# Schematic.net
KiCad netlist of a schematic drawn in EAGLE
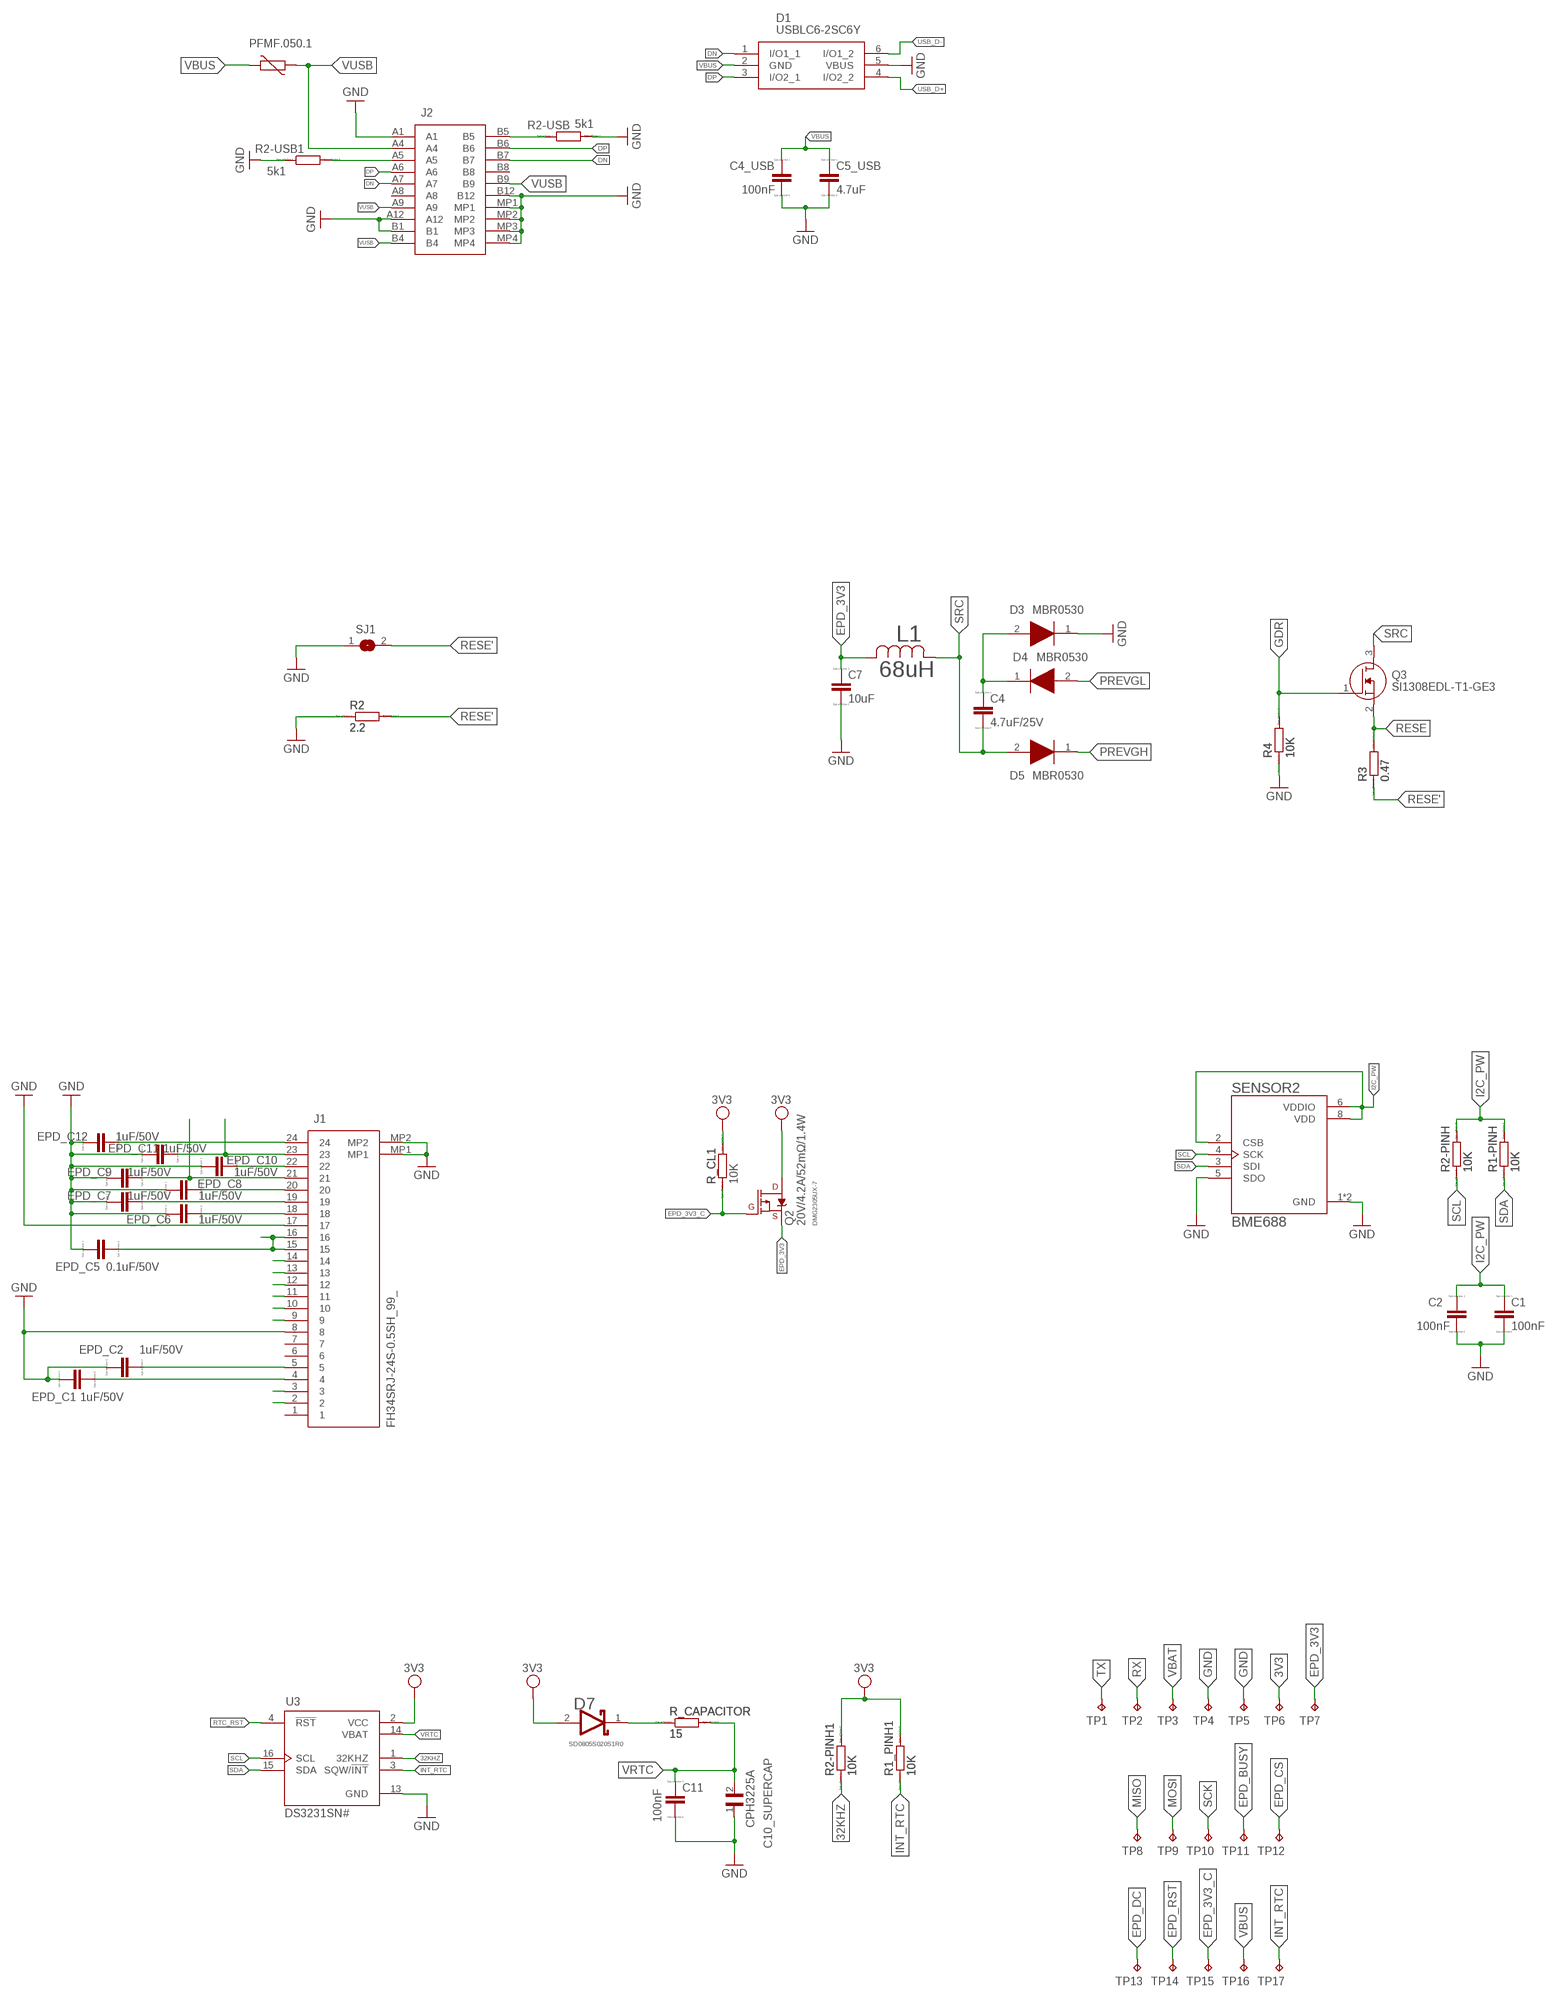
[diagram p0: schematic, sheet 1, part 1 of 2]
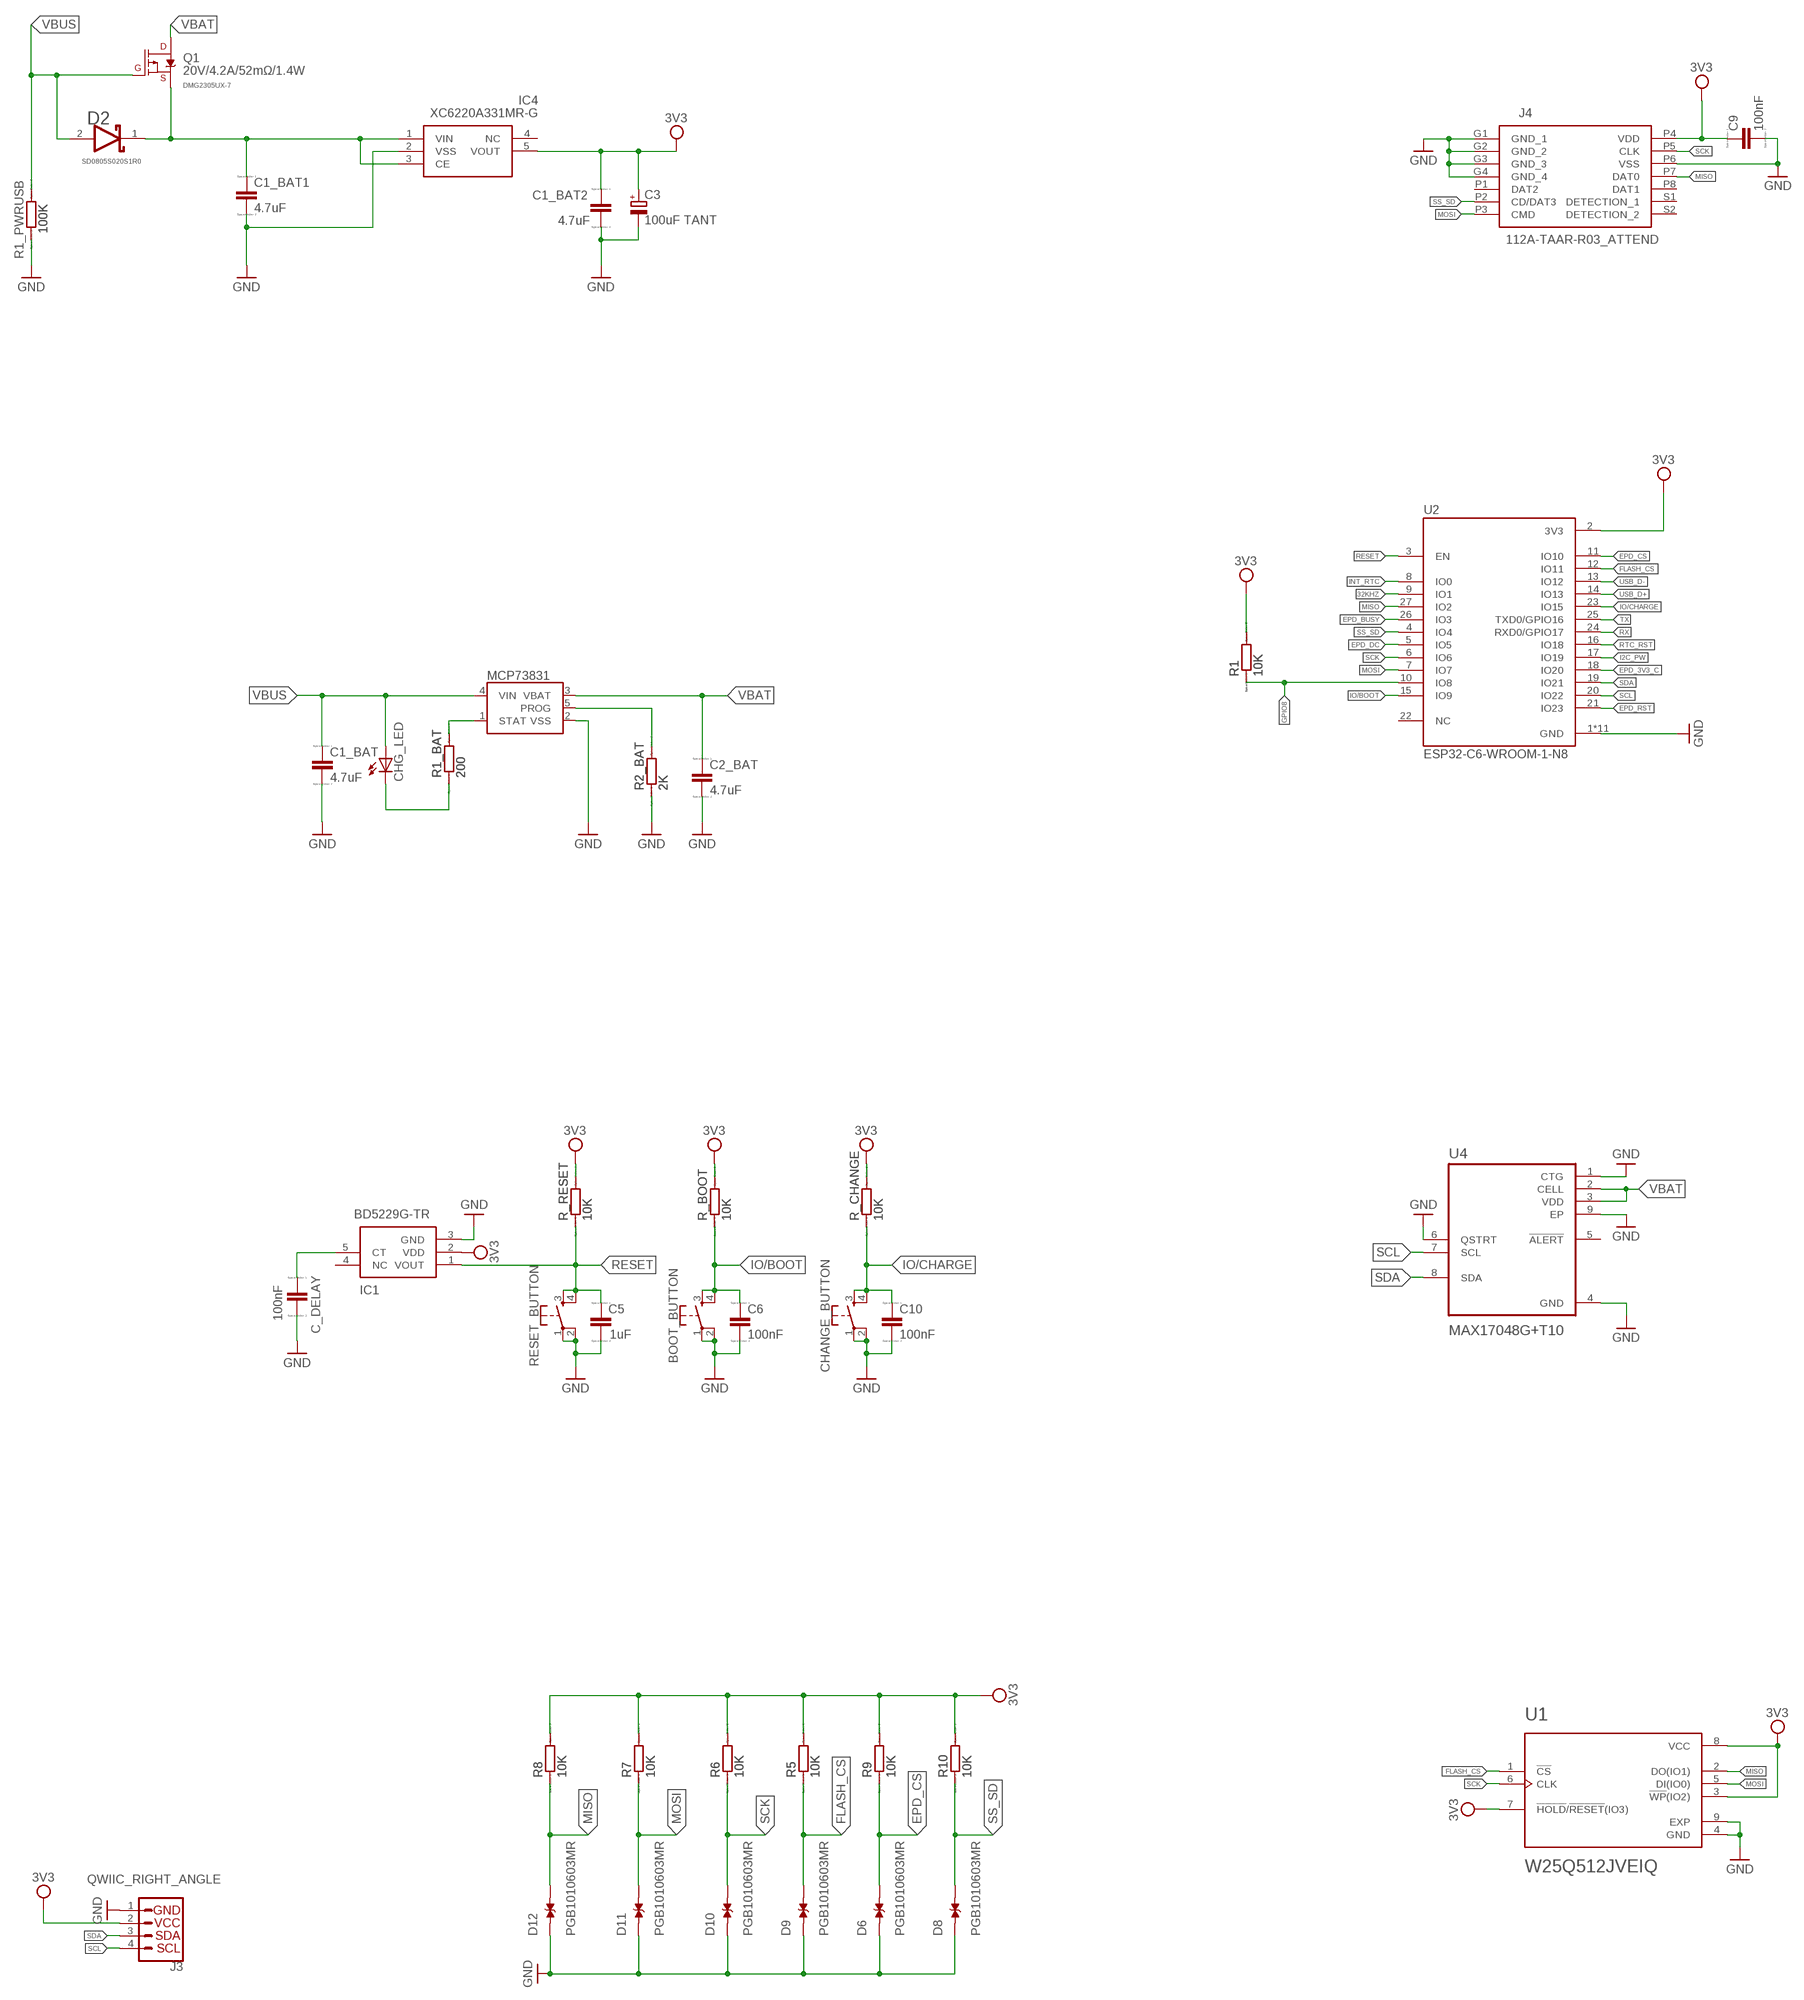
[diagram p1: schematic, sheet 1, part 2 of 2]

(export (version "E")
  (design (tool "Eeschema 10.0.6"))
  (components
    (comp (ref "BOOT_BUTTON")
      (value "BUTTON_CUSYOMV1")
      (footprint "eagle-import:MYBUTTON")
      (libsource (lib "eagle-import") (part "BUTTON_CUSYOMV1"))
    )
    (comp (ref "C1")
      (value "100nF")
      (footprint "eagle-import:EAGLE-LTSPICE_C0402")
      (libsource (lib "eagle-import") (part "EAGLE-LTSPICE_CC0402"))
    )
    (comp (ref "C1_BAT")
      (value "4.7uF")
      (footprint "eagle-import:EAGLE-LTSPICE_C0402")
      (libsource (lib "eagle-import") (part "EAGLE-LTSPICE_CC0402"))
    )
    (comp (ref "C1_BAT1")
      (value "4.7uF")
      (footprint "eagle-import:EAGLE-LTSPICE_C0402")
      (libsource (lib "eagle-import") (part "EAGLE-LTSPICE_CC0402"))
    )
    (comp (ref "C1_BAT2")
      (value "4.7uF")
      (footprint "eagle-import:EAGLE-LTSPICE_C0402")
      (libsource (lib "eagle-import") (part "EAGLE-LTSPICE_CC0402"))
    )
    (comp (ref "C2")
      (value "100nF")
      (footprint "eagle-import:EAGLE-LTSPICE_C0402")
      (libsource (lib "eagle-import") (part "EAGLE-LTSPICE_CC0402"))
    )
    (comp (ref "C2_BAT")
      (value "4.7uF")
      (footprint "eagle-import:EAGLE-LTSPICE_C0402")
      (libsource (lib "eagle-import") (part "EAGLE-LTSPICE_CC0402"))
    )
    (comp (ref "C3")
      (value "100uF TANT")
      (footprint "eagle-import:RCL_CT3528")
      (libsource (lib "eagle-import") (part "RCL_CPOL-EUCT3528"))
    )
    (comp (ref "C4")
      (value "4.7uF/25V")
      (footprint "eagle-import:ESP32_WROVER_EAGLE-LTSPICE_C0402")
      (libsource (lib "eagle-import") (part "ESP32_WROVER_EAGLE-LTSPICE_CC0402"))
    )
    (comp (ref "C4_USB")
      (value "100nF")
      (footprint "eagle-import:EAGLE-LTSPICE_C0402")
      (libsource (lib "eagle-import") (part "EAGLE-LTSPICE_CC0402"))
    )
    (comp (ref "C5")
      (value "1uF")
      (footprint "eagle-import:EAGLE-LTSPICE_C0402")
      (libsource (lib "eagle-import") (part "EAGLE-LTSPICE_CC0402"))
    )
    (comp (ref "C5_USB")
      (value "4.7uF")
      (footprint "eagle-import:EAGLE-LTSPICE_C0402")
      (libsource (lib "eagle-import") (part "EAGLE-LTSPICE_CC0402"))
    )
    (comp (ref "C6")
      (value "100nF")
      (footprint "eagle-import:EAGLE-LTSPICE_C0402")
      (libsource (lib "eagle-import") (part "EAGLE-LTSPICE_CC0402"))
    )
    (comp (ref "C7")
      (value "10uF")
      (footprint "eagle-import:ESP32_WROVER_EAGLE-LTSPICE_C0402")
      (libsource (lib "eagle-import") (part "ESP32_WROVER_EAGLE-LTSPICE_CC0402"))
    )
    (comp (ref "C9")
      (value "100nF")
      (footprint "eagle-import:ESP32_WROVER_EAGLE-LTSPICE_C0402")
      (libsource (lib "eagle-import") (part "ESP32_WROVER_EAGLE-LTSPICE_CC0402"))
    )
    (comp (ref "C10")
      (value "100nF")
      (footprint "eagle-import:EAGLE-LTSPICE_C0402")
      (libsource (lib "eagle-import") (part "EAGLE-LTSPICE_CC0402"))
    )
    (comp (ref "C10_SUPERCAP")
      (value "CPH3225A")
      (footprint "eagle-import:CAPCP3225X100N")
      (fields (field (name "MF") "Seiko Instruments"))
      (libsource (lib "eagle-import") (part "CPH3225A"))
    )
    (comp (ref "C11")
      (value "100nF")
      (footprint "eagle-import:EAGLE-LTSPICE_C0402")
      (libsource (lib "eagle-import") (part "EAGLE-LTSPICE_CC0402"))
    )
    (comp (ref "CHANGE_BUTTON")
      (value "BUTTON_CUSYOMV1")
      (footprint "eagle-import:MYBUTTON")
      (libsource (lib "eagle-import") (part "BUTTON_CUSYOMV1"))
    )
    (comp (ref "CHG_LED")
      (value "ADAFRUIT_LEDCHIP-LED0603")
      (footprint "eagle-import:ADAFRUIT_CHIP-LED0603")
      (libsource (lib "eagle-import") (part "ADAFRUIT_LEDCHIP-LED0603"))
    )
    (comp (ref "C_DELAY")
      (value "100nF")
      (footprint "eagle-import:EAGLE-LTSPICE_C0402")
      (libsource (lib "eagle-import") (part "EAGLE-LTSPICE_CC0402"))
    )
    (comp (ref "D1")
      (value "USBLC6-2SC6Y")
      (footprint "eagle-import:SOT95P280X145-6N")
      (fields (field (name "MF") "STMicroelectronics"))
      (libsource (lib "eagle-import") (part "USBLC6-2SC6Y"))
    )
    (comp (ref "D2")
      (value "SD0805S020S1R0")
      (footprint "eagle-import:ESP32_WROVER_AVX---SD0805S020S1R0_AVX_SD0805S020S1R0_0")
      (fields
        (field (name "DIGIKEY_PART_NUMBER") "478-7800-1-ND")
        (field (name "MF") "AVX")
        (field (name "MOUSER_PART_NUMBER") "581-SD0805S020S1R0")
      )
      (libsource (lib "eagle-import") (part "ESP32_WROVER_AVX---SD0805S020S1R0_AVX_SD0805S020S1R0_0_0AVX_SD0805S020S1R0_0_0"))
    )
    (comp (ref "D3")
      (value "MBR0530")
      (footprint "eagle-import:SOD3716X135N")
      (fields (field (name "MF") "ON Semiconductor"))
      (libsource (lib "eagle-import") (part "MBR0530"))
    )
    (comp (ref "D4")
      (value "MBR0530")
      (footprint "eagle-import:SOD3716X135N")
      (fields (field (name "MF") "ON Semiconductor"))
      (libsource (lib "eagle-import") (part "MBR0530"))
    )
    (comp (ref "D5")
      (value "MBR0530")
      (footprint "eagle-import:SOD3716X135N")
      (fields (field (name "MF") "ON Semiconductor"))
      (libsource (lib "eagle-import") (part "MBR0530"))
    )
    (comp (ref "D6")
      (value "PGB1010603MR")
      (footprint "eagle-import:DIOC1608X36N")
      (fields (field (name "MF") "Littelfuse Inc."))
      (libsource (lib "eagle-import") (part "PGB1010603MR"))
    )
    (comp (ref "D7")
      (value "SD0805S020S1R0")
      (footprint "eagle-import:ESP32_WROVER_AVX---SD0805S020S1R0_AVX_SD0805S020S1R0_0")
      (fields
        (field (name "DIGIKEY_PART_NUMBER") "478-7800-1-ND")
        (field (name "MF") "AVX")
        (field (name "MOUSER_PART_NUMBER") "581-SD0805S020S1R0")
      )
      (libsource (lib "eagle-import") (part "ESP32_WROVER_AVX---SD0805S020S1R0_AVX_SD0805S020S1R0_0_0AVX_SD0805S020S1R0_0_0"))
    )
    (comp (ref "D8")
      (value "PGB1010603MR")
      (footprint "eagle-import:DIOC1608X36N")
      (fields (field (name "MF") "Littelfuse Inc."))
      (libsource (lib "eagle-import") (part "PGB1010603MR"))
    )
    (comp (ref "D9")
      (value "PGB1010603MR")
      (footprint "eagle-import:DIOC1608X36N")
      (fields (field (name "MF") "Littelfuse Inc."))
      (libsource (lib "eagle-import") (part "PGB1010603MR"))
    )
    (comp (ref "D10")
      (value "PGB1010603MR")
      (footprint "eagle-import:DIOC1608X36N")
      (fields (field (name "MF") "Littelfuse Inc."))
      (libsource (lib "eagle-import") (part "PGB1010603MR"))
    )
    (comp (ref "D11")
      (value "PGB1010603MR")
      (footprint "eagle-import:DIOC1608X36N")
      (fields (field (name "MF") "Littelfuse Inc."))
      (libsource (lib "eagle-import") (part "PGB1010603MR"))
    )
    (comp (ref "D12")
      (value "PGB1010603MR")
      (footprint "eagle-import:DIOC1608X36N")
      (fields (field (name "MF") "Littelfuse Inc."))
      (libsource (lib "eagle-import") (part "PGB1010603MR"))
    )
    (comp (ref "EPD_C1")
      (value "1uF/50V")
      (footprint "eagle-import:EAGLE-LTSPICE_C0402")
      (libsource (lib "eagle-import") (part "EAGLE-LTSPICE_CC0402"))
    )
    (comp (ref "EPD_C2")
      (value "1uF/50V")
      (footprint "eagle-import:EAGLE-LTSPICE_C0402")
      (libsource (lib "eagle-import") (part "EAGLE-LTSPICE_CC0402"))
    )
    (comp (ref "EPD_C5")
      (value "0.1uF/50V")
      (footprint "eagle-import:EAGLE-LTSPICE_C0402")
      (libsource (lib "eagle-import") (part "EAGLE-LTSPICE_CC0402"))
    )
    (comp (ref "EPD_C6")
      (value "1uF/50V")
      (footprint "eagle-import:EAGLE-LTSPICE_C0402")
      (libsource (lib "eagle-import") (part "EAGLE-LTSPICE_CC0402"))
    )
    (comp (ref "EPD_C7")
      (value "1uF/50V")
      (footprint "eagle-import:EAGLE-LTSPICE_C0402")
      (libsource (lib "eagle-import") (part "EAGLE-LTSPICE_CC0402"))
    )
    (comp (ref "EPD_C8")
      (value "1uF/50V")
      (footprint "eagle-import:EAGLE-LTSPICE_C0402")
      (libsource (lib "eagle-import") (part "EAGLE-LTSPICE_CC0402"))
    )
    (comp (ref "EPD_C9")
      (value "1uF/50V")
      (footprint "eagle-import:EAGLE-LTSPICE_C0402")
      (libsource (lib "eagle-import") (part "EAGLE-LTSPICE_CC0402"))
    )
    (comp (ref "EPD_C10")
      (value "1uF/50V")
      (footprint "eagle-import:EAGLE-LTSPICE_C0402")
      (libsource (lib "eagle-import") (part "EAGLE-LTSPICE_CC0402"))
    )
    (comp (ref "EPD_C11")
      (value "1uF/50V")
      (footprint "eagle-import:EAGLE-LTSPICE_C0402")
      (libsource (lib "eagle-import") (part "EAGLE-LTSPICE_CC0402"))
    )
    (comp (ref "EPD_C12")
      (value "1uF/50V")
      (footprint "eagle-import:EAGLE-LTSPICE_C0402")
      (libsource (lib "eagle-import") (part "EAGLE-LTSPICE_CC0402"))
    )
    (comp (ref "IC1")
      (value "BD5229G-TR")
      (footprint "eagle-import:SOT95P280X125-5N")
      (fields (field (name "MOUSER_PART_NUMBER") "755-BD5229G-TR"))
      (libsource (lib "eagle-import") (part "BD5229G-TR"))
    )
    (comp (ref "IC4")
      (value "XC6220A331MR-G")
      (footprint "eagle-import:SOT95P280X120-5N")
      (fields (field (name "MOUSER_PART_NUMBER") "865-XC6220A331MR-G"))
      (libsource (lib "eagle-import") (part "XC6220A331MR-G"))
    )
    (comp (ref "J1")
      (value "FH34SRJ-24S-0.5SH_99_")
      (footprint "eagle-import:FH34SRJ24S05SH99")
      (fields
        (field (name "MANUFACTURER_PART_NUMBER") "FH34SRJ-24S-0.5SH(99)")
        (field (name "MOUSER_PART_NUMBER") "798-FH34SRJ24S05SH99")
      )
      (libsource (lib "eagle-import") (part "FH34SRJ-24S-0.5SH_99_"))
    )
    (comp (ref "J2")
      (value "SAMACSYS_PARTS_USB4110-GF-A")
      (footprint "eagle-import:SAMACSYS_PARTS_USB4110GFA")
      (fields
        (field (name "MANUFACTURER_PART_NUMBER") "USB4110-GF-A")
        (field (name "MOUSER_PART_NUMBER") "640-USB4110-GF-A")
      )
      (libsource (lib "eagle-import") (part "SAMACSYS_PARTS_USB4110-GF-A"))
    )
    (comp (ref "J3")
      (value "QWIIC_RIGHT_ANGLE")
      (footprint "eagle-import:JST04_1MM_RA")
      (libsource (lib "eagle-import") (part "QWIIC_CONNECTORJS-1MM"))
    )
    (comp (ref "J4")
      (value "112A-TAAR-R03_ATTEND")
      (footprint "eagle-import:112ATAARR03ATTEND")
      (fields (field (name "MANUFACTURER_PART_NUMBER") "112A-TAAR-R03 ATTEND"))
      (libsource (lib "eagle-import") (part "112A-TAAR-R03_ATTEND"))
    )
    (comp (ref "L1")
      (value "68uH")
      (footprint "eagle-import:IND_4828-WE-TPC_WRE")
      (fields
        (field (name "MANUFACTURER_PART_NUMBER") "744043680")
        (field (name "COPYRIGHT") "Copyright (C) 2024 Ultra Librarian. All rights reserved.")
      )
      (libsource (lib "eagle-import") (part "744043680IND_4828-WE-TPC_WRE"))
    )
    (comp (ref "MCP73831")
      (value "ESP32_WROVER_SPARKFUN-IC-POWER_MCP73831")
      (footprint "eagle-import:ESP32_WROVER_SPARKFUN-IC-POWER_SOT23-5")
      (libsource (lib "eagle-import") (part "ESP32_WROVER_SPARKFUN-IC-POWER_MCP73831"))
    )
    (comp (ref "PFMF.050.1")
      (value "ESP32C6_VARISTORCN1812")
      (footprint "eagle-import:ESP32C6_VARISTOR_CT_CN1812")
      (libsource (lib "eagle-import") (part "ESP32C6_VARISTORCN1812"))
    )
    (comp (ref "Q1")
      (value "20V/4.2A/52mΩ/1.4W")
      (footprint "eagle-import:ESP32_WROVER_SPARKFUN-DISCRETESEMI_SOT23-3")
      (libsource (lib "eagle-import") (part "ESP32_WROVER_SPARKFUN-DISCRETESEMI_MOSFET_PCH-DMG2305UX-7"))
    )
    (comp (ref "Q2")
      (value "20V/4.2A/52mΩ/1.4W")
      (footprint "eagle-import:ESP32_WROVER_SPARKFUN-DISCRETESEMI_SOT23-3")
      (libsource (lib "eagle-import") (part "ESP32_WROVER_SPARKFUN-DISCRETESEMI_MOSFET_PCH-DMG2305UX-7"))
    )
    (comp (ref "Q3")
      (value "SI1308EDL-T1-GE3")
      (footprint "eagle-import:SOT65P210X110-3N")
      (fields (field (name "MF") "Vishay Siliconix"))
      (libsource (lib "eagle-import") (part "SI1308EDL-T1-GE3"))
    )
    (comp (ref "R1")
      (value "10K")
      (footprint "eagle-import:ESP32_WROVER_EAGLE-LTSPICE_R0402")
      (libsource (lib "eagle-import") (part "ESP32_WROVER_EAGLE-LTSPICE_RR0402"))
    )
    (comp (ref "R1-PINH")
      (value "10K")
      (footprint "eagle-import:ESP32_WROVER_EAGLE-LTSPICE_R0402")
      (libsource (lib "eagle-import") (part "ESP32_WROVER_EAGLE-LTSPICE_RR0402"))
    )
    (comp (ref "R1_BAT")
      (value "200")
      (footprint "eagle-import:ESP32_WROVER_EAGLE-LTSPICE_R0402")
      (libsource (lib "eagle-import") (part "ESP32_WROVER_EAGLE-LTSPICE_RR0402"))
    )
    (comp (ref "R1_PINH1")
      (value "10K")
      (footprint "eagle-import:ESP32_WROVER_EAGLE-LTSPICE_R0402")
      (libsource (lib "eagle-import") (part "ESP32_WROVER_EAGLE-LTSPICE_RR0402"))
    )
    (comp (ref "R1_PWRUSB")
      (value "100K")
      (footprint "eagle-import:ESP32_WROVER_EAGLE-LTSPICE_R0402")
      (libsource (lib "eagle-import") (part "ESP32_WROVER_EAGLE-LTSPICE_RR0402"))
    )
    (comp (ref "R2")
      (value "2.2")
      (footprint "eagle-import:ESP32_WROVER_EAGLE-LTSPICE_R0402")
      (libsource (lib "eagle-import") (part "ESP32_WROVER_EAGLE-LTSPICE_RR0402"))
    )
    (comp (ref "R2-PINH")
      (value "10K")
      (footprint "eagle-import:ESP32_WROVER_EAGLE-LTSPICE_R0402")
      (libsource (lib "eagle-import") (part "ESP32_WROVER_EAGLE-LTSPICE_RR0402"))
    )
    (comp (ref "R2-PINH1")
      (value "10K")
      (footprint "eagle-import:ESP32_WROVER_EAGLE-LTSPICE_R0402")
      (libsource (lib "eagle-import") (part "ESP32_WROVER_EAGLE-LTSPICE_RR0402"))
    )
    (comp (ref "R2-USB")
      (value "5k1")
      (footprint "eagle-import:ESP32_WROVER_EAGLE-LTSPICE_R0402")
      (libsource (lib "eagle-import") (part "ESP32_WROVER_EAGLE-LTSPICE_RR0402"))
    )
    (comp (ref "R2-USB1")
      (value "5k1")
      (footprint "eagle-import:ESP32_WROVER_EAGLE-LTSPICE_R0402")
      (libsource (lib "eagle-import") (part "ESP32_WROVER_EAGLE-LTSPICE_RR0402"))
    )
    (comp (ref "R2_BAT")
      (value "2K")
      (footprint "eagle-import:ESP32_WROVER_EAGLE-LTSPICE_R0402")
      (libsource (lib "eagle-import") (part "ESP32_WROVER_EAGLE-LTSPICE_RR0402"))
    )
    (comp (ref "R3")
      (value "0.47")
      (footprint "eagle-import:ESP32_WROVER_EAGLE-LTSPICE_R0402")
      (libsource (lib "eagle-import") (part "ESP32_WROVER_EAGLE-LTSPICE_RR0402"))
    )
    (comp (ref "R4")
      (value "10K")
      (footprint "eagle-import:ESP32_WROVER_EAGLE-LTSPICE_R0402")
      (libsource (lib "eagle-import") (part "ESP32_WROVER_EAGLE-LTSPICE_RR0402"))
    )
    (comp (ref "R5")
      (value "10K")
      (footprint "eagle-import:ESP32_WROVER_EAGLE-LTSPICE_R0402")
      (libsource (lib "eagle-import") (part "ESP32_WROVER_EAGLE-LTSPICE_RR0402"))
    )
    (comp (ref "R6")
      (value "10K")
      (footprint "eagle-import:ESP32_WROVER_EAGLE-LTSPICE_R0402")
      (libsource (lib "eagle-import") (part "ESP32_WROVER_EAGLE-LTSPICE_RR0402"))
    )
    (comp (ref "R7")
      (value "10K")
      (footprint "eagle-import:ESP32_WROVER_EAGLE-LTSPICE_R0402")
      (libsource (lib "eagle-import") (part "ESP32_WROVER_EAGLE-LTSPICE_RR0402"))
    )
    (comp (ref "R8")
      (value "10K")
      (footprint "eagle-import:ESP32_WROVER_EAGLE-LTSPICE_R0402")
      (libsource (lib "eagle-import") (part "ESP32_WROVER_EAGLE-LTSPICE_RR0402"))
    )
    (comp (ref "R9")
      (value "10K")
      (footprint "eagle-import:ESP32_WROVER_EAGLE-LTSPICE_R0402")
      (libsource (lib "eagle-import") (part "ESP32_WROVER_EAGLE-LTSPICE_RR0402"))
    )
    (comp (ref "R10")
      (value "10K")
      (footprint "eagle-import:ESP32_WROVER_EAGLE-LTSPICE_R0402")
      (libsource (lib "eagle-import") (part "ESP32_WROVER_EAGLE-LTSPICE_RR0402"))
    )
    (comp (ref "RESET_BUTTON")
      (value "BUTTON_CUSYOMV1")
      (footprint "eagle-import:MYBUTTON")
      (libsource (lib "eagle-import") (part "BUTTON_CUSYOMV1"))
    )
    (comp (ref "R_BOOT")
      (value "10K")
      (footprint "eagle-import:ESP32_WROVER_EAGLE-LTSPICE_R0402")
      (libsource (lib "eagle-import") (part "ESP32_WROVER_EAGLE-LTSPICE_RR0402"))
    )
    (comp (ref "R_CAPACITOR")
      (value "15")
      (footprint "eagle-import:ESP32_WROVER_EAGLE-LTSPICE_R0402")
      (libsource (lib "eagle-import") (part "ESP32_WROVER_EAGLE-LTSPICE_RR0402"))
    )
    (comp (ref "R_CHANGE")
      (value "10K")
      (footprint "eagle-import:ESP32_WROVER_EAGLE-LTSPICE_R0402")
      (libsource (lib "eagle-import") (part "ESP32_WROVER_EAGLE-LTSPICE_RR0402"))
    )
    (comp (ref "R_CL1")
      (value "10K")
      (footprint "eagle-import:ESP32_WROVER_EAGLE-LTSPICE_R0402")
      (libsource (lib "eagle-import") (part "ESP32_WROVER_EAGLE-LTSPICE_RR0402"))
    )
    (comp (ref "R_RESET")
      (value "10K")
      (footprint "eagle-import:ESP32_WROVER_EAGLE-LTSPICE_R0402")
      (libsource (lib "eagle-import") (part "ESP32_WROVER_EAGLE-LTSPICE_RR0402"))
    )
    (comp (ref "SENSOR2")
      (value "BME688")
      (footprint "eagle-import:ESP32_WROVER_BME680_PSON80P300X300X100-8N")
      (fields (field (name "MF") "Bosch Sensortec") (field (name "MP") "BME680"))
      (libsource (lib "eagle-import") (part "ESP32_WROVER_BME680_BME680"))
    )
    (comp (ref "SJ1") (value "SJ") (footprint "eagle-import:SJ") (libsource (lib "eagle-import") (part "SJ")))
    (comp (ref "TP1")
      (value "TPTP20R")
      (footprint "eagle-import:TP20R")
      (libsource (lib "eagle-import") (part "TPTP20R"))
    )
    (comp (ref "TP2")
      (value "TPTP20R")
      (footprint "eagle-import:TP20R")
      (libsource (lib "eagle-import") (part "TPTP20R"))
    )
    (comp (ref "TP3")
      (value "TPTP20R")
      (footprint "eagle-import:TP20R")
      (libsource (lib "eagle-import") (part "TPTP20R"))
    )
    (comp (ref "TP4")
      (value "TPTP20R")
      (footprint "eagle-import:TP20R")
      (libsource (lib "eagle-import") (part "TPTP20R"))
    )
    (comp (ref "TP5")
      (value "TPTP20R")
      (footprint "eagle-import:TP20R")
      (libsource (lib "eagle-import") (part "TPTP20R"))
    )
    (comp (ref "TP6")
      (value "TPTP20R")
      (footprint "eagle-import:TP20R")
      (libsource (lib "eagle-import") (part "TPTP20R"))
    )
    (comp (ref "TP7")
      (value "TPTP20R")
      (footprint "eagle-import:TP20R")
      (libsource (lib "eagle-import") (part "TPTP20R"))
    )
    (comp (ref "TP8")
      (value "TPTP20R")
      (footprint "eagle-import:TP20R")
      (libsource (lib "eagle-import") (part "TPTP20R"))
    )
    (comp (ref "TP9")
      (value "TPTP20R")
      (footprint "eagle-import:TP20R")
      (libsource (lib "eagle-import") (part "TPTP20R"))
    )
    (comp (ref "TP10")
      (value "TPTP20R")
      (footprint "eagle-import:TP20R")
      (libsource (lib "eagle-import") (part "TPTP20R"))
    )
    (comp (ref "TP11")
      (value "TPTP20R")
      (footprint "eagle-import:TP20R")
      (libsource (lib "eagle-import") (part "TPTP20R"))
    )
    (comp (ref "TP12")
      (value "TPTP20R")
      (footprint "eagle-import:TP20R")
      (libsource (lib "eagle-import") (part "TPTP20R"))
    )
    (comp (ref "TP13")
      (value "TPTP20R")
      (footprint "eagle-import:TP20R")
      (libsource (lib "eagle-import") (part "TPTP20R"))
    )
    (comp (ref "TP14")
      (value "TPTP20R")
      (footprint "eagle-import:TP20R")
      (libsource (lib "eagle-import") (part "TPTP20R"))
    )
    (comp (ref "TP15")
      (value "TPTP20R")
      (footprint "eagle-import:TP20R")
      (libsource (lib "eagle-import") (part "TPTP20R"))
    )
    (comp (ref "TP16")
      (value "TPTP20R")
      (footprint "eagle-import:TP20R")
      (libsource (lib "eagle-import") (part "TPTP20R"))
    )
    (comp (ref "TP17")
      (value "TPTP20R")
      (footprint "eagle-import:TP20R")
      (libsource (lib "eagle-import") (part "TPTP20R"))
    )
    (comp (ref "U1")
      (value "W25Q512JVEIQ")
      (footprint "eagle-import:SON127P600X800X80-9N")
      (fields (field (name "MF") "Winbond Electronics"))
      (libsource (lib "eagle-import") (part "W25Q512JVEIQ"))
    )
    (comp (ref "U2")
      (value "ESP32-C6-WROOM-1-N8")
      (footprint "eagle-import:XCVR_ESP32-C6-WROOM-1-N8")
      (fields (field (name "MF") "Espressif Systems"))
      (libsource (lib "eagle-import") (part "ESP32-C6-WROOM-1-N8"))
    )
    (comp (ref "U3")
      (value "DS3231SN#")
      (footprint "eagle-import:SOIC127P1032X265-16N")
      (fields (field (name "MF") "Analog Devices"))
      (libsource (lib "eagle-import") (part "DS3231SN#"))
    )
    (comp (ref "U4")
      (value "MAX17048G+T10")
      (footprint "eagle-import:SON50P200X200X80-9N")
      (fields (field (name "MF") "Analog Devices"))
      (libsource (lib "eagle-import") (part "MAX17048G+T10"))
    )
  )
  (nets
    (net (code "1") (name "3V3") (class "Default")
      (node (ref "C1_BAT2") (pin "1") (pinfunction "1_1") (pintype "passive"))
      (node (ref "C3") (pin "+") (pinfunction "+_+") (pintype "passive"))
      (node (ref "C9") (pin "1") (pinfunction "1_1") (pintype "passive"))
      (node (ref "D7") (pin "2") (pinfunction "ANODE_2") (pintype "bidirectional"))
      (node (ref "IC1") (pin "2") (pinfunction "VDD_2") (pintype "bidirectional"))
      (node (ref "IC4") (pin "5") (pinfunction "VOUT_5") (pintype "bidirectional"))
      (node (ref "J3") (pin "2") (pinfunction "2_2") (pintype "power_in"))
      (node (ref "J4") (pin "P4") (pinfunction "VDD_P4") (pintype "bidirectional"))
      (node (ref "Q2") (pin "3") (pinfunction "D_3") (pintype "bidirectional"))
      (node (ref "R1") (pin "2") (pinfunction "2_2") (pintype "passive"))
      (node (ref "R10") (pin "2") (pinfunction "2_2") (pintype "passive"))
      (node (ref "R1_PINH1") (pin "2") (pinfunction "2_2") (pintype "passive"))
      (node (ref "R2-PINH1") (pin "2") (pinfunction "2_2") (pintype "passive"))
      (node (ref "R5") (pin "2") (pinfunction "2_2") (pintype "passive"))
      (node (ref "R6") (pin "2") (pinfunction "2_2") (pintype "passive"))
      (node (ref "R7") (pin "2") (pinfunction "2_2") (pintype "passive"))
      (node (ref "R8") (pin "2") (pinfunction "2_2") (pintype "passive"))
      (node (ref "R9") (pin "2") (pinfunction "2_2") (pintype "passive"))
      (node (ref "R_BOOT") (pin "2") (pinfunction "2_2") (pintype "passive"))
      (node (ref "R_CHANGE") (pin "2") (pinfunction "2_2") (pintype "passive"))
      (node (ref "R_CL1") (pin "2") (pinfunction "2_2") (pintype "passive"))
      (node (ref "R_RESET") (pin "2") (pinfunction "2_2") (pintype "passive"))
      (node (ref "TP6") (pin "TP") (pinfunction "TP_TP") (pintype "input"))
      (node (ref "U1") (pin "3") (pinfunction "~{WP}(IO2)_3") (pintype "bidirectional"))
      (node (ref "U1") (pin "7") (pinfunction "~{HOLD}/~{RESET}(IO3)_7") (pintype "bidirectional"))
      (node (ref "U1") (pin "8") (pinfunction "VCC_8") (pintype "power_in"))
      (node (ref "U2") (pin "2") (pinfunction "3V3_2") (pintype "power_in"))
      (node (ref "U3") (pin "2") (pinfunction "VCC_2") (pintype "power_in"))
    )
    (net (code "2") (name "32KHZ") (class "Default")
      (node (ref "R2-PINH1") (pin "1") (pinfunction "1_1") (pintype "passive"))
      (node (ref "U2") (pin "9") (pinfunction "IO1_9") (pintype "bidirectional"))
      (node (ref "U3") (pin "1") (pinfunction "32KHZ_1") (pintype "output"))
    )
    (net (code "3") (name "DN") (class "Default")
      (node (ref "D1") (pin "1") (pinfunction "I/O1_1_1") (pintype "bidirectional"))
      (node (ref "J2") (pin "A7") (pinfunction "A7_A7") (pintype "bidirectional"))
      (node (ref "J2") (pin "B7") (pinfunction "B7_B7") (pintype "bidirectional"))
    )
    (net (code "4") (name "DP") (class "Default")
      (node (ref "D1") (pin "3") (pinfunction "I/O2_1_3") (pintype "bidirectional"))
      (node (ref "J2") (pin "A6") (pinfunction "A6_A6") (pintype "bidirectional"))
      (node (ref "J2") (pin "B6") (pinfunction "B6_B6") (pintype "bidirectional"))
    )
    (net (code "5") (name "EPD_3V3") (class "Default")
      (node (ref "C7") (pin "1") (pinfunction "1_1") (pintype "passive"))
      (node (ref "L1") (pin "2") (pinfunction "2_2") (pintype "passive"))
      (node (ref "Q2") (pin "2") (pinfunction "S_2") (pintype "bidirectional"))
      (node (ref "TP7") (pin "TP") (pinfunction "TP_TP") (pintype "input"))
    )
    (net (code "6") (name "EPD_3V3_C") (class "Default")
      (node (ref "Q2") (pin "1") (pinfunction "G_1") (pintype "bidirectional"))
      (node (ref "R_CL1") (pin "1") (pinfunction "1_1") (pintype "passive"))
      (node (ref "TP15") (pin "TP") (pinfunction "TP_TP") (pintype "input"))
      (node (ref "U2") (pin "18") (pinfunction "IO20_18") (pintype "bidirectional"))
    )
    (net (code "7") (name "EPD_BUSY") (class "Default")
      (node (ref "TP11") (pin "TP") (pinfunction "TP_TP") (pintype "input"))
      (node (ref "U2") (pin "26") (pinfunction "IO3_26") (pintype "bidirectional"))
    )
    (net (code "8") (name "EPD_CS") (class "Default")
      (node (ref "D6") (pin "2") (pinfunction "2_2") (pintype "passive"))
      (node (ref "R9") (pin "1") (pinfunction "1_1") (pintype "passive"))
      (node (ref "TP12") (pin "TP") (pinfunction "TP_TP") (pintype "input"))
      (node (ref "U2") (pin "11") (pinfunction "IO10_11") (pintype "bidirectional"))
    )
    (net (code "9") (name "EPD_DC") (class "Default")
      (node (ref "TP13") (pin "TP") (pinfunction "TP_TP") (pintype "input"))
      (node (ref "U2") (pin "5") (pinfunction "IO5_5") (pintype "bidirectional"))
    )
    (net (code "10") (name "EPD_RST") (class "Default")
      (node (ref "TP14") (pin "TP") (pinfunction "TP_TP") (pintype "input"))
      (node (ref "U2") (pin "21") (pinfunction "IO23_21") (pintype "bidirectional"))
    )
    (net (code "11") (name "FLASH_CS") (class "Default")
      (node (ref "D9") (pin "2") (pinfunction "2_2") (pintype "passive"))
      (node (ref "R5") (pin "1") (pinfunction "1_1") (pintype "passive"))
      (node (ref "U1") (pin "1") (pinfunction "~{CS}_1") (pintype "input"))
      (node (ref "U2") (pin "12") (pinfunction "IO11_12") (pintype "bidirectional"))
    )
    (net (code "12") (name "GDR") (class "Default")
      (node (ref "Q3") (pin "1") (pinfunction "G_1") (pintype "bidirectional"))
      (node (ref "R4") (pin "2") (pinfunction "2_2") (pintype "passive"))
    )
    (net (code "13") (name "GND") (class "Default")
      (node (ref "BOOT_BUTTON") (pin "1") (pinfunction "1_1") (pintype "passive"))
      (node (ref "BOOT_BUTTON") (pin "2") (pinfunction "2_2") (pintype "passive"))
      (node (ref "C1") (pin "2") (pinfunction "2_2") (pintype "passive"))
      (node (ref "C10") (pin "2") (pinfunction "2_2") (pintype "passive"))
      (node (ref "C10_SUPERCAP") (pin "1") (pinfunction "1_1") (pintype "passive"))
      (node (ref "C11") (pin "2") (pinfunction "2_2") (pintype "passive"))
      (node (ref "C1_BAT") (pin "2") (pinfunction "2_2") (pintype "passive"))
      (node (ref "C1_BAT1") (pin "2") (pinfunction "2_2") (pintype "passive"))
      (node (ref "C1_BAT2") (pin "2") (pinfunction "2_2") (pintype "passive"))
      (node (ref "C2") (pin "2") (pinfunction "2_2") (pintype "passive"))
      (node (ref "C2_BAT") (pin "2") (pinfunction "2_2") (pintype "passive"))
      (node (ref "C3") (pin "-") (pinfunction "-_-") (pintype "passive"))
      (node (ref "C4_USB") (pin "2") (pinfunction "2_2") (pintype "passive"))
      (node (ref "C5") (pin "2") (pinfunction "2_2") (pintype "passive"))
      (node (ref "C5_USB") (pin "2") (pinfunction "2_2") (pintype "passive"))
      (node (ref "C6") (pin "2") (pinfunction "2_2") (pintype "passive"))
      (node (ref "C7") (pin "2") (pinfunction "2_2") (pintype "passive"))
      (node (ref "C9") (pin "2") (pinfunction "2_2") (pintype "passive"))
      (node (ref "CHANGE_BUTTON") (pin "1") (pinfunction "1_1") (pintype "passive"))
      (node (ref "CHANGE_BUTTON") (pin "2") (pinfunction "2_2") (pintype "passive"))
      (node (ref "C_DELAY") (pin "2") (pinfunction "2_2") (pintype "passive"))
      (node (ref "D1") (pin "5") (pinfunction "VBUS_5") (pintype "bidirectional"))
      (node (ref "D10") (pin "1") (pinfunction "1_1") (pintype "passive"))
      (node (ref "D11") (pin "1") (pinfunction "1_1") (pintype "passive"))
      (node (ref "D12") (pin "1") (pinfunction "1_1") (pintype "passive"))
      (node (ref "D3") (pin "1") (pinfunction "K_1") (pintype "bidirectional"))
      (node (ref "D6") (pin "1") (pinfunction "1_1") (pintype "passive"))
      (node (ref "D8") (pin "1") (pinfunction "1_1") (pintype "passive"))
      (node (ref "D9") (pin "1") (pinfunction "1_1") (pintype "passive"))
      (node (ref "EPD_C1") (pin "1") (pinfunction "1_1") (pintype "passive"))
      (node (ref "EPD_C10") (pin "1") (pinfunction "1_1") (pintype "passive"))
      (node (ref "EPD_C11") (pin "1") (pinfunction "1_1") (pintype "passive"))
      (node (ref "EPD_C12") (pin "1") (pinfunction "1_1") (pintype "passive"))
      (node (ref "EPD_C2") (pin "1") (pinfunction "1_1") (pintype "passive"))
      (node (ref "EPD_C5") (pin "1") (pinfunction "1_1") (pintype "passive"))
      (node (ref "EPD_C6") (pin "1") (pinfunction "1_1") (pintype "passive"))
      (node (ref "EPD_C7") (pin "1") (pinfunction "1_1") (pintype "passive"))
      (node (ref "EPD_C8") (pin "1") (pinfunction "1_1") (pintype "passive"))
      (node (ref "EPD_C9") (pin "1") (pinfunction "1_1") (pintype "passive"))
      (node (ref "IC1") (pin "3") (pinfunction "GND_3") (pintype "bidirectional"))
      (node (ref "IC4") (pin "2") (pinfunction "VSS_2") (pintype "bidirectional"))
      (node (ref "J1") (pin "17") (pinfunction "17_17") (pintype "bidirectional"))
      (node (ref "J1") (pin "8") (pinfunction "8_8") (pintype "bidirectional"))
      (node (ref "J1") (pin "MP1") (pinfunction "MP1_MP1") (pintype "bidirectional"))
      (node (ref "J1") (pin "MP2") (pinfunction "MP2_MP2") (pintype "bidirectional"))
      (node (ref "J2") (pin "A1") (pinfunction "A1_A1") (pintype "bidirectional"))
      (node (ref "J2") (pin "A12") (pinfunction "A12_A12") (pintype "bidirectional"))
      (node (ref "J2") (pin "B1") (pinfunction "B1_B1") (pintype "bidirectional"))
      (node (ref "J2") (pin "B12") (pinfunction "B12_B12") (pintype "bidirectional"))
      (node (ref "J2") (pin "MP1") (pinfunction "MP1_MP1") (pintype "bidirectional"))
      (node (ref "J2") (pin "MP2") (pinfunction "MP2_MP2") (pintype "bidirectional"))
      (node (ref "J2") (pin "MP3") (pinfunction "MP3_MP3") (pintype "bidirectional"))
      (node (ref "J2") (pin "MP4") (pinfunction "MP4_MP4") (pintype "bidirectional"))
      (node (ref "J3") (pin "1") (pinfunction "1_1") (pintype "power_in"))
      (node (ref "J4") (pin "G1") (pinfunction "GND_1_G1") (pintype "bidirectional"))
      (node (ref "J4") (pin "G2") (pinfunction "GND_2_G2") (pintype "bidirectional"))
      (node (ref "J4") (pin "G3") (pinfunction "GND_3_G3") (pintype "bidirectional"))
      (node (ref "J4") (pin "G4") (pinfunction "GND_4_G4") (pintype "bidirectional"))
      (node (ref "J4") (pin "P6") (pinfunction "VSS_P6") (pintype "bidirectional"))
      (node (ref "MCP73831") (pin "2") (pinfunction "VSS_2") (pintype "power_in"))
      (node (ref "R1_PWRUSB") (pin "1") (pinfunction "1_1") (pintype "passive"))
      (node (ref "R2") (pin "1") (pinfunction "1_1") (pintype "passive"))
      (node (ref "R2-USB") (pin "2") (pinfunction "2_2") (pintype "passive"))
      (node (ref "R2-USB1") (pin "1") (pinfunction "1_1") (pintype "passive"))
      (node (ref "R2_BAT") (pin "1") (pinfunction "1_1") (pintype "passive"))
      (node (ref "R4") (pin "1") (pinfunction "1_1") (pintype "passive"))
      (node (ref "RESET_BUTTON") (pin "1") (pinfunction "1_1") (pintype "passive"))
      (node (ref "RESET_BUTTON") (pin "2") (pinfunction "2_2") (pintype "passive"))
      (node (ref "SENSOR2") (pin "1") (pinfunction "GND_1") (pintype "power_in"))
      (node (ref "SENSOR2") (pin "5") (pinfunction "SDO_5") (pintype "bidirectional"))
      (node (ref "SENSOR2") (pin "7") (pinfunction "GND_7") (pintype "power_in"))
      (node (ref "SJ1") (pin "1") (pinfunction "1_1") (pintype "passive"))
      (node (ref "TP4") (pin "TP") (pinfunction "TP_TP") (pintype "input"))
      (node (ref "TP5") (pin "TP") (pinfunction "TP_TP") (pintype "input"))
      (node (ref "U1") (pin "4") (pinfunction "GND_4") (pintype "power_in"))
      (node (ref "U1") (pin "9") (pinfunction "EXP_9") (pintype "passive"))
      (node (ref "U2") (pin "1") (pinfunction "GND_1") (pintype "power_in"))
      (node (ref "U2") (pin "28") (pinfunction "GND_28") (pintype "power_in"))
      (node (ref "U2") (pin "29_1") (pinfunction "GND_29_1") (pintype "power_in"))
      (node (ref "U2") (pin "29_2") (pinfunction "GND_29_2") (pintype "power_in"))
      (node (ref "U2") (pin "29_3") (pinfunction "GND_29_3") (pintype "power_in"))
      (node (ref "U2") (pin "29_4") (pinfunction "GND_29_4") (pintype "power_in"))
      (node (ref "U2") (pin "29_5") (pinfunction "GND_29_5") (pintype "power_in"))
      (node (ref "U2") (pin "29_6") (pinfunction "GND_29_6") (pintype "power_in"))
      (node (ref "U2") (pin "29_7") (pinfunction "GND_29_7") (pintype "power_in"))
      (node (ref "U2") (pin "29_8") (pinfunction "GND_29_8") (pintype "power_in"))
      (node (ref "U2") (pin "29_9") (pinfunction "GND_29_9") (pintype "power_in"))
      (node (ref "U3") (pin "13") (pinfunction "GND_13") (pintype "power_in"))
      (node (ref "U4") (pin "1") (pinfunction "CTG_1") (pintype "power_in"))
      (node (ref "U4") (pin "4") (pinfunction "GND_4") (pintype "power_in"))
      (node (ref "U4") (pin "6") (pinfunction "QSTRT_6") (pintype "input"))
      (node (ref "U4") (pin "9") (pinfunction "EP_9") (pintype "power_in"))
    )
    (net (code "14") (name "GPIO8") (class "Default")
      (node (ref "R1") (pin "1") (pinfunction "1_1") (pintype "passive"))
      (node (ref "U2") (pin "10") (pinfunction "IO8_10") (pintype "bidirectional"))
    )
    (net (code "15") (name "I2C_PW") (class "Default")
      (node (ref "C1") (pin "1") (pinfunction "1_1") (pintype "passive"))
      (node (ref "C2") (pin "1") (pinfunction "1_1") (pintype "passive"))
      (node (ref "R1-PINH") (pin "2") (pinfunction "2_2") (pintype "passive"))
      (node (ref "R2-PINH") (pin "2") (pinfunction "2_2") (pintype "passive"))
      (node (ref "SENSOR2") (pin "2") (pinfunction "CSB_2") (pintype "input"))
      (node (ref "SENSOR2") (pin "6") (pinfunction "VDDIO_6") (pintype "power_in"))
      (node (ref "SENSOR2") (pin "8") (pinfunction "VDD_8") (pintype "power_in"))
      (node (ref "U2") (pin "17") (pinfunction "IO19_17") (pintype "bidirectional"))
    )
    (net (code "16") (name "INT_RTC") (class "Default")
      (node (ref "R1_PINH1") (pin "1") (pinfunction "1_1") (pintype "passive"))
      (node (ref "TP17") (pin "TP") (pinfunction "TP_TP") (pintype "input"))
      (node (ref "U2") (pin "8") (pinfunction "IO0_8") (pintype "bidirectional"))
      (node (ref "U3") (pin "3") (pinfunction "SQW/~{INT}_3") (pintype "output"))
    )
    (net (code "17") (name "IO{slash}BOOT") (class "Default")
      (node (ref "BOOT_BUTTON") (pin "3") (pinfunction "3_3") (pintype "passive"))
      (node (ref "BOOT_BUTTON") (pin "4") (pinfunction "4_4") (pintype "passive"))
      (node (ref "C6") (pin "1") (pinfunction "1_1") (pintype "passive"))
      (node (ref "R_BOOT") (pin "1") (pinfunction "1_1") (pintype "passive"))
      (node (ref "U2") (pin "15") (pinfunction "IO9_15") (pintype "bidirectional"))
    )
    (net (code "18") (name "IO{slash}CHARGE") (class "Default")
      (node (ref "C10") (pin "1") (pinfunction "1_1") (pintype "passive"))
      (node (ref "CHANGE_BUTTON") (pin "3") (pinfunction "3_3") (pintype "passive"))
      (node (ref "CHANGE_BUTTON") (pin "4") (pinfunction "4_4") (pintype "passive"))
      (node (ref "R_CHANGE") (pin "1") (pinfunction "1_1") (pintype "passive"))
      (node (ref "U2") (pin "23") (pinfunction "IO15_23") (pintype "bidirectional"))
    )
    (net (code "19") (name "MISO") (class "Default")
      (node (ref "D12") (pin "2") (pinfunction "2_2") (pintype "passive"))
      (node (ref "J4") (pin "P7") (pinfunction "DAT0_P7") (pintype "bidirectional"))
      (node (ref "R8") (pin "1") (pinfunction "1_1") (pintype "passive"))
      (node (ref "TP8") (pin "TP") (pinfunction "TP_TP") (pintype "input"))
      (node (ref "U1") (pin "2") (pinfunction "DO(IO1)_2") (pintype "bidirectional"))
      (node (ref "U2") (pin "27") (pinfunction "IO2_27") (pintype "bidirectional"))
    )
    (net (code "20") (name "MOSI") (class "Default")
      (node (ref "D11") (pin "2") (pinfunction "2_2") (pintype "passive"))
      (node (ref "J4") (pin "P3") (pinfunction "CMD_P3") (pintype "bidirectional"))
      (node (ref "R7") (pin "1") (pinfunction "1_1") (pintype "passive"))
      (node (ref "TP9") (pin "TP") (pinfunction "TP_TP") (pintype "input"))
      (node (ref "U1") (pin "5") (pinfunction "DI(IO0)_5") (pintype "bidirectional"))
      (node (ref "U2") (pin "7") (pinfunction "IO7_7") (pintype "bidirectional"))
    )
    (net (code "21") (name "Net-(CHG_LED-PadC)") (class "Default")
      (node (ref "CHG_LED") (pin "C") (pinfunction "C_C") (pintype "passive"))
      (node (ref "R1_BAT") (pin "1") (pinfunction "1_1") (pintype "passive"))
    )
    (net (code "22") (name "Net-(D2-CATHODE)") (class "Default")
      (node (ref "C1_BAT1") (pin "1") (pinfunction "1_1") (pintype "passive"))
      (node (ref "D2") (pin "1") (pinfunction "CATHODE_1") (pintype "bidirectional"))
      (node (ref "IC4") (pin "1") (pinfunction "VIN_1") (pintype "bidirectional"))
      (node (ref "IC4") (pin "3") (pinfunction "CE_3") (pintype "bidirectional"))
      (node (ref "Q1") (pin "2") (pinfunction "S_2") (pintype "bidirectional"))
    )
    (net (code "23") (name "Net-(D3-A)") (class "Default")
      (node (ref "C4") (pin "1") (pinfunction "1_1") (pintype "passive"))
      (node (ref "D3") (pin "2") (pinfunction "A_2") (pintype "bidirectional"))
      (node (ref "D4") (pin "1") (pinfunction "K_1") (pintype "bidirectional"))
    )
    (net (code "24") (name "Net-(D7-CATHODE)") (class "Default")
      (node (ref "D7") (pin "1") (pinfunction "CATHODE_1") (pintype "bidirectional"))
      (node (ref "R_CAPACITOR") (pin "1") (pinfunction "1_1") (pintype "passive"))
    )
    (net (code "25") (name "Net-(EPD_C1-Pad2)") (class "Default")
      (node (ref "EPD_C1") (pin "2") (pinfunction "2_2") (pintype "passive"))
      (node (ref "J1") (pin "4") (pinfunction "4_4") (pintype "bidirectional"))
    )
    (net (code "26") (name "Net-(EPD_C2-Pad2)") (class "Default")
      (node (ref "EPD_C2") (pin "2") (pinfunction "2_2") (pintype "passive"))
      (node (ref "J1") (pin "5") (pinfunction "5_5") (pintype "bidirectional"))
    )
    (net (code "27") (name "Net-(EPD_C5-Pad2)") (class "Default")
      (node (ref "EPD_C5") (pin "2") (pinfunction "2_2") (pintype "passive"))
      (node (ref "J1") (pin "15") (pinfunction "15_15") (pintype "bidirectional"))
      (node (ref "J1") (pin "16") (pinfunction "16_16") (pintype "bidirectional"))
    )
    (net (code "28") (name "Net-(EPD_C6-Pad2)") (class "Default")
      (node (ref "EPD_C6") (pin "2") (pinfunction "2_2") (pintype "passive"))
      (node (ref "J1") (pin "18") (pinfunction "18_18") (pintype "bidirectional"))
    )
    (net (code "29") (name "Net-(EPD_C7-Pad2)") (class "Default")
      (node (ref "EPD_C7") (pin "2") (pinfunction "2_2") (pintype "passive"))
      (node (ref "J1") (pin "19") (pinfunction "19_19") (pintype "bidirectional"))
    )
    (net (code "30") (name "Net-(EPD_C8-Pad2)") (class "Default")
      (node (ref "EPD_C8") (pin "2") (pinfunction "2_2") (pintype "passive"))
      (node (ref "J1") (pin "20") (pinfunction "20_20") (pintype "bidirectional"))
    )
    (net (code "31") (name "Net-(EPD_C9-Pad2)") (class "Default")
      (node (ref "EPD_C9") (pin "2") (pinfunction "2_2") (pintype "passive"))
      (node (ref "J1") (pin "21") (pinfunction "21_21") (pintype "bidirectional"))
    )
    (net (code "32") (name "Net-(EPD_C10-Pad2)") (class "Default")
      (node (ref "EPD_C10") (pin "2") (pinfunction "2_2") (pintype "passive"))
      (node (ref "J1") (pin "22") (pinfunction "22_22") (pintype "bidirectional"))
    )
    (net (code "33") (name "Net-(EPD_C11-Pad2)") (class "Default")
      (node (ref "EPD_C11") (pin "2") (pinfunction "2_2") (pintype "passive"))
      (node (ref "J1") (pin "23") (pinfunction "23_23") (pintype "bidirectional"))
    )
    (net (code "34") (name "Net-(EPD_C12-Pad2)") (class "Default")
      (node (ref "EPD_C12") (pin "2") (pinfunction "2_2") (pintype "passive"))
      (node (ref "J1") (pin "24") (pinfunction "24_24") (pintype "bidirectional"))
    )
    (net (code "35") (name "Net-(IC1-CT)") (class "Default")
      (node (ref "C_DELAY") (pin "1") (pinfunction "1_1") (pintype "passive"))
      (node (ref "IC1") (pin "5") (pinfunction "CT_5") (pintype "bidirectional"))
    )
    (net (code "36") (name "Net-(J2-PadA5)") (class "Default")
      (node (ref "J2") (pin "A5") (pinfunction "A5_A5") (pintype "bidirectional"))
      (node (ref "R2-USB1") (pin "2") (pinfunction "2_2") (pintype "passive"))
    )
    (net (code "37") (name "Net-(J2-PadB5)") (class "Default")
      (node (ref "J2") (pin "B5") (pinfunction "B5_B5") (pintype "bidirectional"))
      (node (ref "R2-USB") (pin "1") (pinfunction "1_1") (pintype "passive"))
    )
    (net (code "38") (name "Net-(MCP73831-PROG)") (class "Default")
      (node (ref "MCP73831") (pin "5") (pinfunction "PROG_5") (pintype "input"))
      (node (ref "R2_BAT") (pin "2") (pinfunction "2_2") (pintype "passive"))
    )
    (net (code "39") (name "Net-(MCP73831-STAT)") (class "Default")
      (node (ref "MCP73831") (pin "1") (pinfunction "STAT_1") (pintype "output"))
      (node (ref "R1_BAT") (pin "2") (pinfunction "2_2") (pintype "passive"))
    )
    (net (code "40") (name "PREVGH") (class "Default")
      (node (ref "D5") (pin "1") (pinfunction "K_1") (pintype "bidirectional"))
    )
    (net (code "41") (name "PREVGL") (class "Default")
      (node (ref "D4") (pin "2") (pinfunction "A_2") (pintype "bidirectional"))
    )
    (net (code "42") (name "RESE") (class "Default")
      (node (ref "Q3") (pin "2") (pinfunction "S_2") (pintype "bidirectional"))
      (node (ref "R3") (pin "2") (pinfunction "2_2") (pintype "passive"))
    )
    (net (code "43") (name "RESE'") (class "Default")
      (node (ref "R2") (pin "2") (pinfunction "2_2") (pintype "passive"))
      (node (ref "R3") (pin "1") (pinfunction "1_1") (pintype "passive"))
      (node (ref "SJ1") (pin "2") (pinfunction "2_2") (pintype "passive"))
    )
    (net (code "44") (name "RESET") (class "Default")
      (node (ref "C5") (pin "1") (pinfunction "1_1") (pintype "passive"))
      (node (ref "IC1") (pin "1") (pinfunction "VOUT_1") (pintype "bidirectional"))
      (node (ref "RESET_BUTTON") (pin "3") (pinfunction "3_3") (pintype "passive"))
      (node (ref "RESET_BUTTON") (pin "4") (pinfunction "4_4") (pintype "passive"))
      (node (ref "R_RESET") (pin "1") (pinfunction "1_1") (pintype "passive"))
      (node (ref "U2") (pin "3") (pinfunction "EN_3") (pintype "input"))
    )
    (net (code "45") (name "RTC_RST") (class "Default")
      (node (ref "U2") (pin "16") (pinfunction "IO18_16") (pintype "bidirectional"))
      (node (ref "U3") (pin "4") (pinfunction "~{RST}_4") (pintype "input"))
    )
    (net (code "46") (name "RX") (class "Default")
      (node (ref "TP2") (pin "TP") (pinfunction "TP_TP") (pintype "input"))
      (node (ref "U2") (pin "24") (pinfunction "RXD0/GPIO17_24") (pintype "bidirectional"))
    )
    (net (code "47") (name "SCK") (class "Default")
      (node (ref "D10") (pin "2") (pinfunction "2_2") (pintype "passive"))
      (node (ref "J4") (pin "P5") (pinfunction "CLK_P5") (pintype "bidirectional"))
      (node (ref "R6") (pin "1") (pinfunction "1_1") (pintype "passive"))
      (node (ref "TP10") (pin "TP") (pinfunction "TP_TP") (pintype "input"))
      (node (ref "U1") (pin "6") (pinfunction "CLK_6") (pintype "input"))
      (node (ref "U2") (pin "6") (pinfunction "IO6_6") (pintype "bidirectional"))
    )
    (net (code "48") (name "SCL") (class "Default")
      (node (ref "J3") (pin "4") (pinfunction "4_4") (pintype "passive"))
      (node (ref "R2-PINH") (pin "1") (pinfunction "1_1") (pintype "passive"))
      (node (ref "SENSOR2") (pin "4") (pinfunction "SCK_4") (pintype "input"))
      (node (ref "U2") (pin "20") (pinfunction "IO22_20") (pintype "bidirectional"))
      (node (ref "U3") (pin "16") (pinfunction "SCL_16") (pintype "input"))
      (node (ref "U4") (pin "7") (pinfunction "SCL_7") (pintype "input"))
    )
    (net (code "49") (name "SDA") (class "Default")
      (node (ref "J3") (pin "3") (pinfunction "3_3") (pintype "passive"))
      (node (ref "R1-PINH") (pin "1") (pinfunction "1_1") (pintype "passive"))
      (node (ref "SENSOR2") (pin "3") (pinfunction "SDI_3") (pintype "bidirectional"))
      (node (ref "U2") (pin "19") (pinfunction "IO21_19") (pintype "bidirectional"))
      (node (ref "U3") (pin "15") (pinfunction "SDA_15") (pintype "bidirectional"))
      (node (ref "U4") (pin "8") (pinfunction "SDA_8") (pintype "bidirectional"))
    )
    (net (code "50") (name "SRC") (class "Default")
      (node (ref "C4") (pin "2") (pinfunction "2_2") (pintype "passive"))
      (node (ref "D5") (pin "2") (pinfunction "A_2") (pintype "bidirectional"))
      (node (ref "L1") (pin "1") (pinfunction "1_1") (pintype "passive"))
      (node (ref "Q3") (pin "3") (pinfunction "D_3") (pintype "bidirectional"))
    )
    (net (code "51") (name "SS_SD") (class "Default")
      (node (ref "D8") (pin "2") (pinfunction "2_2") (pintype "passive"))
      (node (ref "J4") (pin "P2") (pinfunction "CD/DAT3_P2") (pintype "bidirectional"))
      (node (ref "R10") (pin "1") (pinfunction "1_1") (pintype "passive"))
      (node (ref "U2") (pin "4") (pinfunction "IO4_4") (pintype "bidirectional"))
    )
    (net (code "52") (name "TX") (class "Default")
      (node (ref "TP1") (pin "TP") (pinfunction "TP_TP") (pintype "input"))
      (node (ref "U2") (pin "25") (pinfunction "TXD0/GPIO16_25") (pintype "bidirectional"))
    )
    (net (code "53") (name "USB_D+") (class "Default")
      (node (ref "D1") (pin "4") (pinfunction "I/O2_2_4") (pintype "bidirectional"))
      (node (ref "U2") (pin "14") (pinfunction "IO13_14") (pintype "bidirectional"))
    )
    (net (code "54") (name "USB_D-") (class "Default")
      (node (ref "D1") (pin "6") (pinfunction "I/O1_2_6") (pintype "bidirectional"))
      (node (ref "U2") (pin "13") (pinfunction "IO12_13") (pintype "bidirectional"))
    )
    (net (code "55") (name "VBAT") (class "Default")
      (node (ref "C2_BAT") (pin "1") (pinfunction "1_1") (pintype "passive"))
      (node (ref "MCP73831") (pin "3") (pinfunction "VBAT_3") (pintype "power_in"))
      (node (ref "Q1") (pin "3") (pinfunction "D_3") (pintype "bidirectional"))
      (node (ref "TP3") (pin "TP") (pinfunction "TP_TP") (pintype "input"))
      (node (ref "U4") (pin "2") (pinfunction "CELL_2") (pintype "power_in"))
      (node (ref "U4") (pin "3") (pinfunction "VDD_3") (pintype "power_in"))
    )
    (net (code "56") (name "VBUS") (class "Default")
      (node (ref "C1_BAT") (pin "1") (pinfunction "1_1") (pintype "passive"))
      (node (ref "C4_USB") (pin "1") (pinfunction "1_1") (pintype "passive"))
      (node (ref "C5_USB") (pin "1") (pinfunction "1_1") (pintype "passive"))
      (node (ref "CHG_LED") (pin "A") (pinfunction "A_A") (pintype "passive"))
      (node (ref "D1") (pin "2") (pinfunction "GND_2") (pintype "bidirectional"))
      (node (ref "D2") (pin "2") (pinfunction "ANODE_2") (pintype "bidirectional"))
      (node (ref "MCP73831") (pin "4") (pinfunction "VIN_4") (pintype "power_in"))
      (node (ref "PFMF.050.1") (pin "2") (pinfunction "2_2") (pintype "passive"))
      (node (ref "Q1") (pin "1") (pinfunction "G_1") (pintype "bidirectional"))
      (node (ref "R1_PWRUSB") (pin "2") (pinfunction "2_2") (pintype "passive"))
      (node (ref "TP16") (pin "TP") (pinfunction "TP_TP") (pintype "input"))
    )
    (net (code "57") (name "VRTC") (class "Default")
      (node (ref "C10_SUPERCAP") (pin "2") (pinfunction "2_2") (pintype "passive"))
      (node (ref "C11") (pin "1") (pinfunction "1_1") (pintype "passive"))
      (node (ref "R_CAPACITOR") (pin "2") (pinfunction "2_2") (pintype "passive"))
      (node (ref "U3") (pin "14") (pinfunction "VBAT_14") (pintype "power_in"))
    )
    (net (code "58") (name "VUSB") (class "Default")
      (node (ref "J2") (pin "A4") (pinfunction "A4_A4") (pintype "bidirectional"))
      (node (ref "J2") (pin "A9") (pinfunction "A9_A9") (pintype "bidirectional"))
      (node (ref "J2") (pin "B4") (pinfunction "B4_B4") (pintype "bidirectional"))
      (node (ref "J2") (pin "B9") (pinfunction "B9_B9") (pintype "bidirectional"))
      (node (ref "PFMF.050.1") (pin "1") (pinfunction "1_1") (pintype "passive"))
    )
    (net (code "59") (name "unconnected-(IC1-NC-Pad4)") (class "Default")
      (node (ref "IC1") (pin "4") (pinfunction "NC_4") (pintype "no_connect"))
    )
    (net (code "60") (name "unconnected-(IC4-NC-Pad4)") (class "Default")
      (node (ref "IC4") (pin "4") (pinfunction "NC_4") (pintype "no_connect"))
    )
    (net (code "61") (name "unconnected-(J1-Pad1)") (class "Default")
      (node (ref "J1") (pin "1") (pinfunction "1_1") (pintype "bidirectional"))
    )
    (net (code "62") (name "unconnected-(J1-Pad2)") (class "Default")
      (node (ref "J1") (pin "2") (pinfunction "2_2") (pintype "bidirectional"))
    )
    (net (code "63") (name "unconnected-(J1-Pad3)") (class "Default")
      (node (ref "J1") (pin "3") (pinfunction "3_3") (pintype "bidirectional"))
    )
    (net (code "64") (name "unconnected-(J1-Pad6)") (class "Default")
      (node (ref "J1") (pin "6") (pinfunction "6_6") (pintype "bidirectional"))
    )
    (net (code "65") (name "unconnected-(J1-Pad7)") (class "Default")
      (node (ref "J1") (pin "7") (pinfunction "7_7") (pintype "bidirectional"))
    )
    (net (code "66") (name "unconnected-(J1-Pad9)") (class "Default")
      (node (ref "J1") (pin "9") (pinfunction "9_9") (pintype "bidirectional"))
    )
    (net (code "67") (name "unconnected-(J1-Pad10)") (class "Default")
      (node (ref "J1") (pin "10") (pinfunction "10_10") (pintype "bidirectional"))
    )
    (net (code "68") (name "unconnected-(J1-Pad11)") (class "Default")
      (node (ref "J1") (pin "11") (pinfunction "11_11") (pintype "bidirectional"))
    )
    (net (code "69") (name "unconnected-(J1-Pad12)") (class "Default")
      (node (ref "J1") (pin "12") (pinfunction "12_12") (pintype "bidirectional"))
    )
    (net (code "70") (name "unconnected-(J1-Pad13)") (class "Default")
      (node (ref "J1") (pin "13") (pinfunction "13_13") (pintype "bidirectional"))
    )
    (net (code "71") (name "unconnected-(J1-Pad14)") (class "Default")
      (node (ref "J1") (pin "14") (pinfunction "14_14") (pintype "bidirectional"))
    )
    (net (code "72") (name "unconnected-(J2-PadA8)") (class "Default")
      (node (ref "J2") (pin "A8") (pinfunction "A8_A8") (pintype "bidirectional"))
    )
    (net (code "73") (name "unconnected-(J2-PadB8)") (class "Default")
      (node (ref "J2") (pin "B8") (pinfunction "B8_B8") (pintype "bidirectional"))
    )
    (net (code "74") (name "unconnected-(J4-DAT1-PadP8)") (class "Default")
      (node (ref "J4") (pin "P8") (pinfunction "DAT1_P8") (pintype "bidirectional"))
    )
    (net (code "75") (name "unconnected-(J4-DAT2-PadP1)") (class "Default")
      (node (ref "J4") (pin "P1") (pinfunction "DAT2_P1") (pintype "bidirectional"))
    )
    (net (code "76") (name "unconnected-(J4-DETECTION_1-PadS1)") (class "Default")
      (node (ref "J4") (pin "S1") (pinfunction "DETECTION_1_S1") (pintype "bidirectional"))
    )
    (net (code "77") (name "unconnected-(J4-DETECTION_2-PadS2)") (class "Default")
      (node (ref "J4") (pin "S2") (pinfunction "DETECTION_2_S2") (pintype "bidirectional"))
    )
    (net (code "78") (name "unconnected-(U2-NC-Pad22)") (class "Default")
      (node (ref "U2") (pin "22") (pinfunction "NC_22") (pintype "no_connect"))
    )
    (net (code "79") (name "unconnected-(U4-~{ALERT}-Pad5)") (class "Default")
      (node (ref "U4") (pin "5") (pinfunction "~{ALERT}_5") (pintype "output"))
    )
  )
)
